# ultimate_Co-Op_v2_0.net
KiCad netlist of a schematic drawn in EAGLE
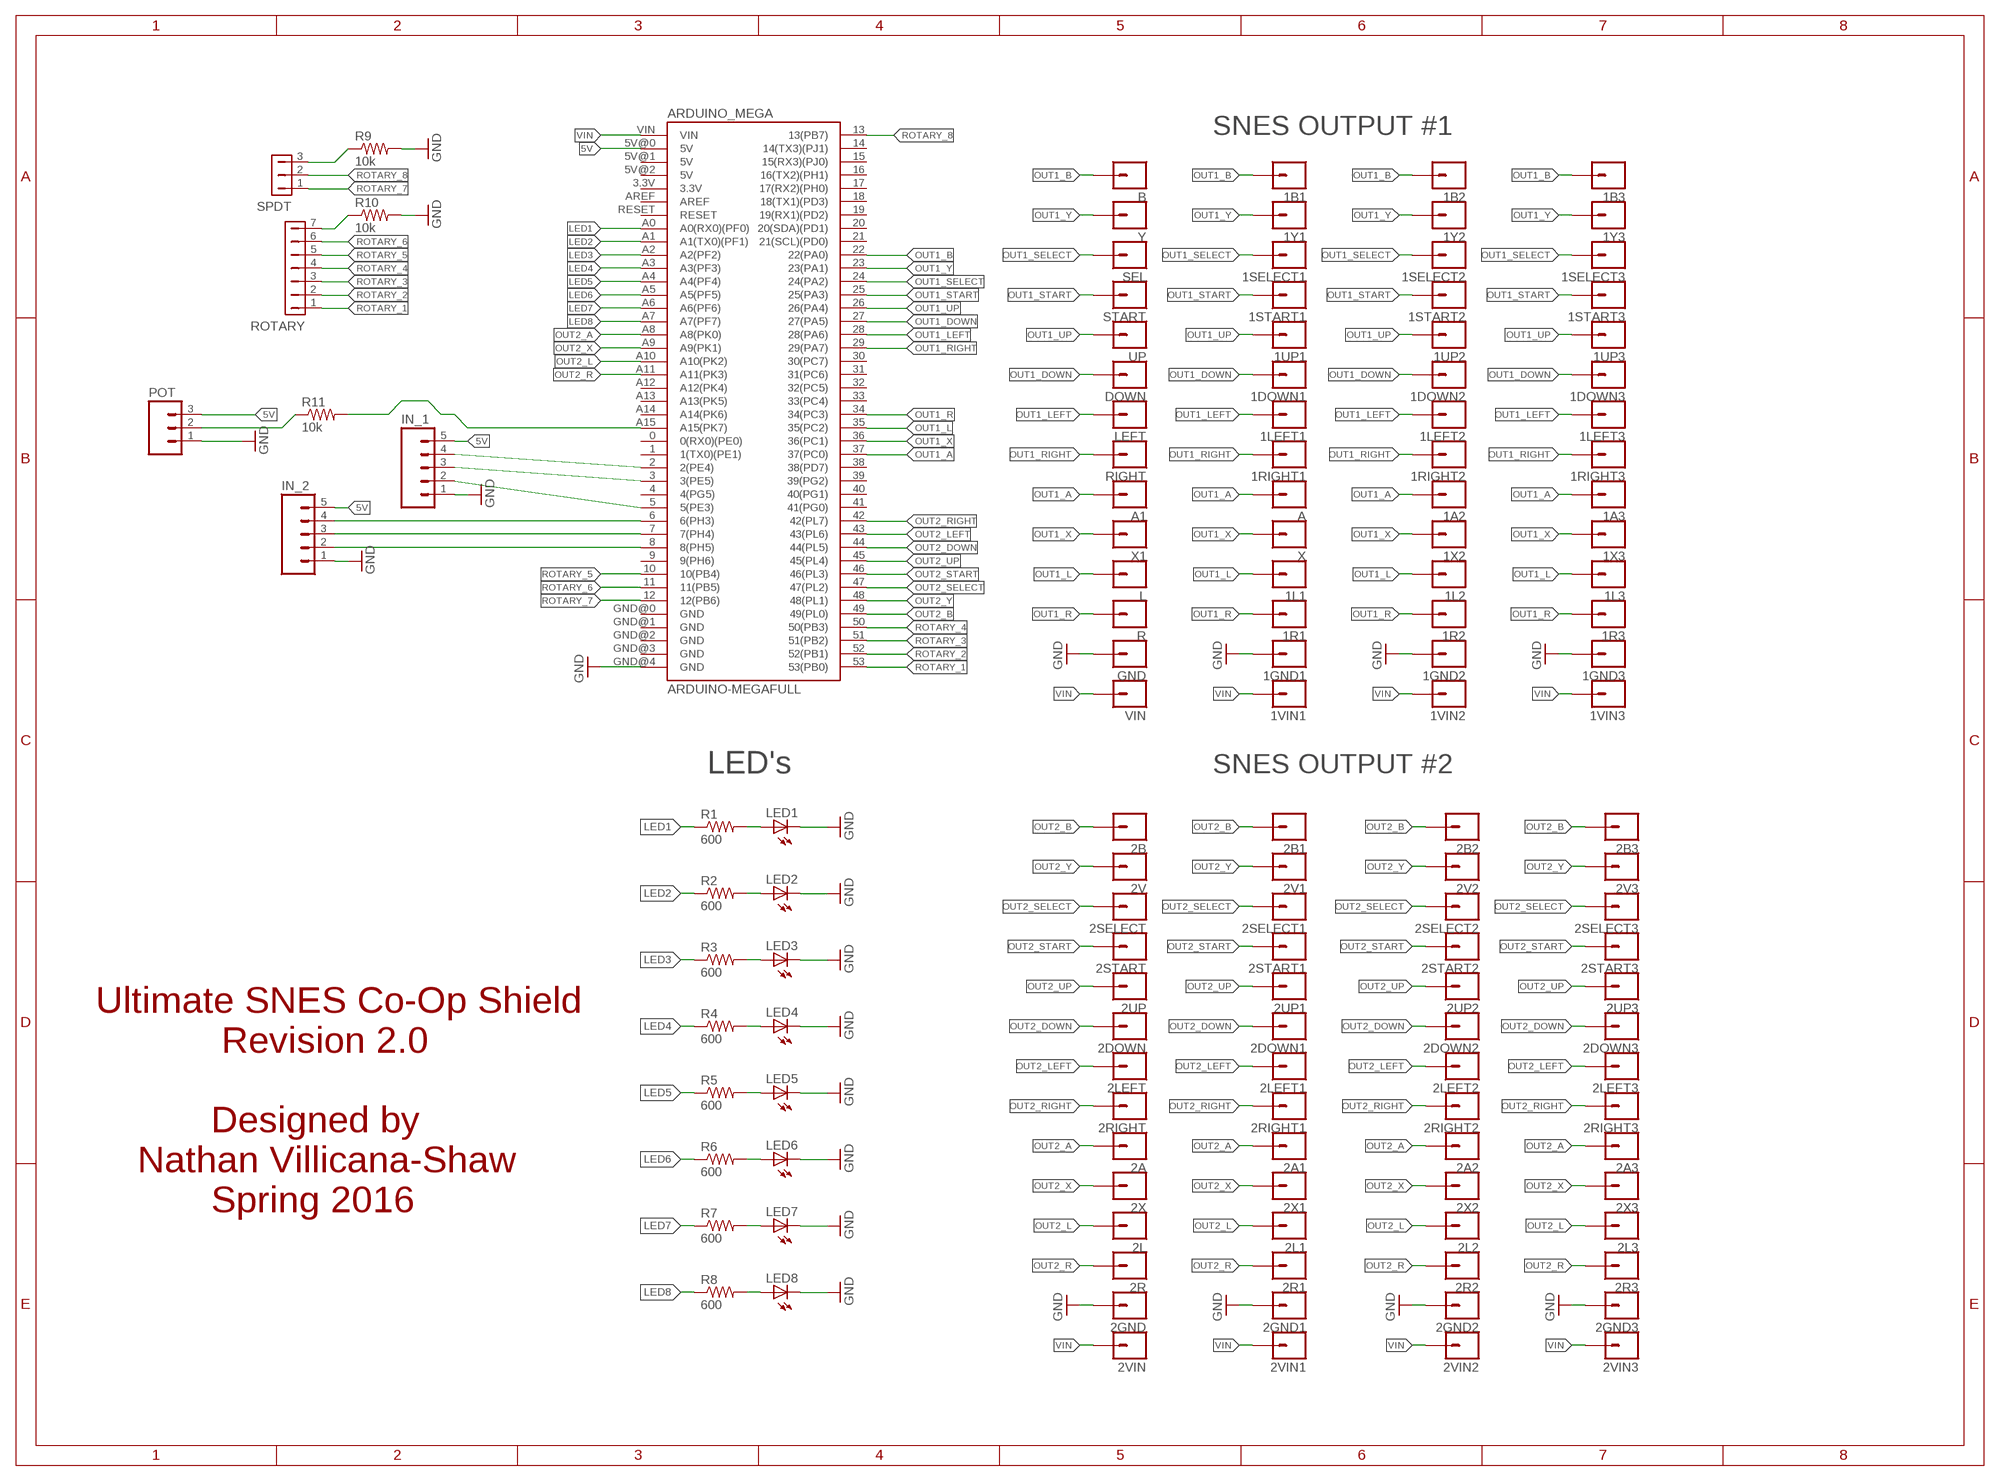
[diagram p0: schematic, sheet 1]

(export (version "E")
  (design (tool "Eeschema 10.0.6"))
  (components
    (comp (ref "1A2")
      (value "M01PTH")
      (footprint "eagle-import:1X01")
      (libsource (lib "eagle-import") (part "M01PTH"))
    )
    (comp (ref "1A3")
      (value "M01PTH")
      (footprint "eagle-import:1X01")
      (libsource (lib "eagle-import") (part "M01PTH"))
    )
    (comp (ref "1B1")
      (value "M01PTH")
      (footprint "eagle-import:1X01")
      (libsource (lib "eagle-import") (part "M01PTH"))
    )
    (comp (ref "1B2")
      (value "M01PTH")
      (footprint "eagle-import:1X01")
      (libsource (lib "eagle-import") (part "M01PTH"))
    )
    (comp (ref "1B3")
      (value "M01PTH")
      (footprint "eagle-import:1X01")
      (libsource (lib "eagle-import") (part "M01PTH"))
    )
    (comp (ref "1DOWN1")
      (value "M01PTH")
      (footprint "eagle-import:1X01")
      (libsource (lib "eagle-import") (part "M01PTH"))
    )
    (comp (ref "1DOWN2")
      (value "M01PTH")
      (footprint "eagle-import:1X01")
      (libsource (lib "eagle-import") (part "M01PTH"))
    )
    (comp (ref "1DOWN3")
      (value "M01PTH")
      (footprint "eagle-import:1X01")
      (libsource (lib "eagle-import") (part "M01PTH"))
    )
    (comp (ref "1GND1")
      (value "M01PTH")
      (footprint "eagle-import:1X01")
      (libsource (lib "eagle-import") (part "M01PTH"))
    )
    (comp (ref "1GND2")
      (value "M01PTH")
      (footprint "eagle-import:1X01")
      (libsource (lib "eagle-import") (part "M01PTH"))
    )
    (comp (ref "1GND3")
      (value "M01PTH")
      (footprint "eagle-import:1X01")
      (libsource (lib "eagle-import") (part "M01PTH"))
    )
    (comp (ref "1L1")
      (value "M01PTH")
      (footprint "eagle-import:1X01")
      (libsource (lib "eagle-import") (part "M01PTH"))
    )
    (comp (ref "1L2")
      (value "M01PTH")
      (footprint "eagle-import:1X01")
      (libsource (lib "eagle-import") (part "M01PTH"))
    )
    (comp (ref "1L3")
      (value "M01PTH")
      (footprint "eagle-import:1X01")
      (libsource (lib "eagle-import") (part "M01PTH"))
    )
    (comp (ref "1LEFT1")
      (value "M01PTH")
      (footprint "eagle-import:1X01")
      (libsource (lib "eagle-import") (part "M01PTH"))
    )
    (comp (ref "1LEFT2")
      (value "M01PTH")
      (footprint "eagle-import:1X01")
      (libsource (lib "eagle-import") (part "M01PTH"))
    )
    (comp (ref "1LEFT3")
      (value "M01PTH")
      (footprint "eagle-import:1X01")
      (libsource (lib "eagle-import") (part "M01PTH"))
    )
    (comp (ref "1R1")
      (value "M01PTH")
      (footprint "eagle-import:1X01")
      (libsource (lib "eagle-import") (part "M01PTH"))
    )
    (comp (ref "1R2")
      (value "M01PTH")
      (footprint "eagle-import:1X01")
      (libsource (lib "eagle-import") (part "M01PTH"))
    )
    (comp (ref "1R3")
      (value "M01PTH")
      (footprint "eagle-import:1X01")
      (libsource (lib "eagle-import") (part "M01PTH"))
    )
    (comp (ref "1RIGHT1")
      (value "M01PTH")
      (footprint "eagle-import:1X01")
      (libsource (lib "eagle-import") (part "M01PTH"))
    )
    (comp (ref "1RIGHT2")
      (value "M01PTH")
      (footprint "eagle-import:1X01")
      (libsource (lib "eagle-import") (part "M01PTH"))
    )
    (comp (ref "1RIGHT3")
      (value "M01PTH")
      (footprint "eagle-import:1X01")
      (libsource (lib "eagle-import") (part "M01PTH"))
    )
    (comp (ref "1SELECT1")
      (value "M01PTH")
      (footprint "eagle-import:1X01")
      (libsource (lib "eagle-import") (part "M01PTH"))
    )
    (comp (ref "1SELECT2")
      (value "M01PTH")
      (footprint "eagle-import:1X01")
      (libsource (lib "eagle-import") (part "M01PTH"))
    )
    (comp (ref "1SELECT3")
      (value "M01PTH")
      (footprint "eagle-import:1X01")
      (libsource (lib "eagle-import") (part "M01PTH"))
    )
    (comp (ref "1START1")
      (value "M01PTH")
      (footprint "eagle-import:1X01")
      (libsource (lib "eagle-import") (part "M01PTH"))
    )
    (comp (ref "1START2")
      (value "M01PTH")
      (footprint "eagle-import:1X01")
      (libsource (lib "eagle-import") (part "M01PTH"))
    )
    (comp (ref "1START3")
      (value "M01PTH")
      (footprint "eagle-import:1X01")
      (libsource (lib "eagle-import") (part "M01PTH"))
    )
    (comp (ref "1UP1")
      (value "M01PTH")
      (footprint "eagle-import:1X01")
      (libsource (lib "eagle-import") (part "M01PTH"))
    )
    (comp (ref "1UP2")
      (value "M01PTH")
      (footprint "eagle-import:1X01")
      (libsource (lib "eagle-import") (part "M01PTH"))
    )
    (comp (ref "1UP3")
      (value "M01PTH")
      (footprint "eagle-import:1X01")
      (libsource (lib "eagle-import") (part "M01PTH"))
    )
    (comp (ref "1VIN1")
      (value "M01PTH")
      (footprint "eagle-import:1X01")
      (libsource (lib "eagle-import") (part "M01PTH"))
    )
    (comp (ref "1VIN2")
      (value "M01PTH")
      (footprint "eagle-import:1X01")
      (libsource (lib "eagle-import") (part "M01PTH"))
    )
    (comp (ref "1VIN3")
      (value "M01PTH")
      (footprint "eagle-import:1X01")
      (libsource (lib "eagle-import") (part "M01PTH"))
    )
    (comp (ref "1X2")
      (value "M01PTH")
      (footprint "eagle-import:1X01")
      (libsource (lib "eagle-import") (part "M01PTH"))
    )
    (comp (ref "1X3")
      (value "M01PTH")
      (footprint "eagle-import:1X01")
      (libsource (lib "eagle-import") (part "M01PTH"))
    )
    (comp (ref "1Y1")
      (value "M01PTH")
      (footprint "eagle-import:1X01")
      (libsource (lib "eagle-import") (part "M01PTH"))
    )
    (comp (ref "1Y2")
      (value "M01PTH")
      (footprint "eagle-import:1X01")
      (libsource (lib "eagle-import") (part "M01PTH"))
    )
    (comp (ref "1Y3")
      (value "M01PTH")
      (footprint "eagle-import:1X01")
      (libsource (lib "eagle-import") (part "M01PTH"))
    )
    (comp (ref "2A")
      (value "M01PTH")
      (footprint "eagle-import:1X01")
      (libsource (lib "eagle-import") (part "M01PTH"))
    )
    (comp (ref "2A1")
      (value "M01PTH")
      (footprint "eagle-import:1X01")
      (libsource (lib "eagle-import") (part "M01PTH"))
    )
    (comp (ref "2A2")
      (value "M01PTH")
      (footprint "eagle-import:1X01")
      (libsource (lib "eagle-import") (part "M01PTH"))
    )
    (comp (ref "2A3")
      (value "M01PTH")
      (footprint "eagle-import:1X01")
      (libsource (lib "eagle-import") (part "M01PTH"))
    )
    (comp (ref "2B")
      (value "M01PTH")
      (footprint "eagle-import:1X01")
      (libsource (lib "eagle-import") (part "M01PTH"))
    )
    (comp (ref "2B1")
      (value "M01PTH")
      (footprint "eagle-import:1X01")
      (libsource (lib "eagle-import") (part "M01PTH"))
    )
    (comp (ref "2B2")
      (value "M01PTH")
      (footprint "eagle-import:1X01")
      (libsource (lib "eagle-import") (part "M01PTH"))
    )
    (comp (ref "2B3")
      (value "M01PTH")
      (footprint "eagle-import:1X01")
      (libsource (lib "eagle-import") (part "M01PTH"))
    )
    (comp (ref "2DOWN")
      (value "M01PTH")
      (footprint "eagle-import:1X01")
      (libsource (lib "eagle-import") (part "M01PTH"))
    )
    (comp (ref "2DOWN1")
      (value "M01PTH")
      (footprint "eagle-import:1X01")
      (libsource (lib "eagle-import") (part "M01PTH"))
    )
    (comp (ref "2DOWN2")
      (value "M01PTH")
      (footprint "eagle-import:1X01")
      (libsource (lib "eagle-import") (part "M01PTH"))
    )
    (comp (ref "2DOWN3")
      (value "M01PTH")
      (footprint "eagle-import:1X01")
      (libsource (lib "eagle-import") (part "M01PTH"))
    )
    (comp (ref "2GND")
      (value "M01PTH")
      (footprint "eagle-import:1X01")
      (libsource (lib "eagle-import") (part "M01PTH"))
    )
    (comp (ref "2GND1")
      (value "M01PTH")
      (footprint "eagle-import:1X01")
      (libsource (lib "eagle-import") (part "M01PTH"))
    )
    (comp (ref "2GND2")
      (value "M01PTH")
      (footprint "eagle-import:1X01")
      (libsource (lib "eagle-import") (part "M01PTH"))
    )
    (comp (ref "2GND3")
      (value "M01PTH")
      (footprint "eagle-import:1X01")
      (libsource (lib "eagle-import") (part "M01PTH"))
    )
    (comp (ref "2L")
      (value "M01PTH")
      (footprint "eagle-import:1X01")
      (libsource (lib "eagle-import") (part "M01PTH"))
    )
    (comp (ref "2L1")
      (value "M01PTH")
      (footprint "eagle-import:1X01")
      (libsource (lib "eagle-import") (part "M01PTH"))
    )
    (comp (ref "2L2")
      (value "M01PTH")
      (footprint "eagle-import:1X01")
      (libsource (lib "eagle-import") (part "M01PTH"))
    )
    (comp (ref "2L3")
      (value "M01PTH")
      (footprint "eagle-import:1X01")
      (libsource (lib "eagle-import") (part "M01PTH"))
    )
    (comp (ref "2LEFT")
      (value "M01PTH")
      (footprint "eagle-import:1X01")
      (libsource (lib "eagle-import") (part "M01PTH"))
    )
    (comp (ref "2LEFT1")
      (value "M01PTH")
      (footprint "eagle-import:1X01")
      (libsource (lib "eagle-import") (part "M01PTH"))
    )
    (comp (ref "2LEFT2")
      (value "M01PTH")
      (footprint "eagle-import:1X01")
      (libsource (lib "eagle-import") (part "M01PTH"))
    )
    (comp (ref "2LEFT3")
      (value "M01PTH")
      (footprint "eagle-import:1X01")
      (libsource (lib "eagle-import") (part "M01PTH"))
    )
    (comp (ref "2R")
      (value "M01PTH")
      (footprint "eagle-import:1X01")
      (libsource (lib "eagle-import") (part "M01PTH"))
    )
    (comp (ref "2R1")
      (value "M01PTH")
      (footprint "eagle-import:1X01")
      (libsource (lib "eagle-import") (part "M01PTH"))
    )
    (comp (ref "2R2")
      (value "M01PTH")
      (footprint "eagle-import:1X01")
      (libsource (lib "eagle-import") (part "M01PTH"))
    )
    (comp (ref "2R3")
      (value "M01PTH")
      (footprint "eagle-import:1X01")
      (libsource (lib "eagle-import") (part "M01PTH"))
    )
    (comp (ref "2RIGHT")
      (value "M01PTH")
      (footprint "eagle-import:1X01")
      (libsource (lib "eagle-import") (part "M01PTH"))
    )
    (comp (ref "2RIGHT1")
      (value "M01PTH")
      (footprint "eagle-import:1X01")
      (libsource (lib "eagle-import") (part "M01PTH"))
    )
    (comp (ref "2RIGHT2")
      (value "M01PTH")
      (footprint "eagle-import:1X01")
      (libsource (lib "eagle-import") (part "M01PTH"))
    )
    (comp (ref "2RIGHT3")
      (value "M01PTH")
      (footprint "eagle-import:1X01")
      (libsource (lib "eagle-import") (part "M01PTH"))
    )
    (comp (ref "2SELECT")
      (value "M01PTH")
      (footprint "eagle-import:1X01")
      (libsource (lib "eagle-import") (part "M01PTH"))
    )
    (comp (ref "2SELECT1")
      (value "M01PTH")
      (footprint "eagle-import:1X01")
      (libsource (lib "eagle-import") (part "M01PTH"))
    )
    (comp (ref "2SELECT2")
      (value "M01PTH")
      (footprint "eagle-import:1X01")
      (libsource (lib "eagle-import") (part "M01PTH"))
    )
    (comp (ref "2SELECT3")
      (value "M01PTH")
      (footprint "eagle-import:1X01")
      (libsource (lib "eagle-import") (part "M01PTH"))
    )
    (comp (ref "2START")
      (value "M01PTH")
      (footprint "eagle-import:1X01")
      (libsource (lib "eagle-import") (part "M01PTH"))
    )
    (comp (ref "2START1")
      (value "M01PTH")
      (footprint "eagle-import:1X01")
      (libsource (lib "eagle-import") (part "M01PTH"))
    )
    (comp (ref "2START2")
      (value "M01PTH")
      (footprint "eagle-import:1X01")
      (libsource (lib "eagle-import") (part "M01PTH"))
    )
    (comp (ref "2START3")
      (value "M01PTH")
      (footprint "eagle-import:1X01")
      (libsource (lib "eagle-import") (part "M01PTH"))
    )
    (comp (ref "2UP")
      (value "M01PTH")
      (footprint "eagle-import:1X01")
      (libsource (lib "eagle-import") (part "M01PTH"))
    )
    (comp (ref "2UP1")
      (value "M01PTH")
      (footprint "eagle-import:1X01")
      (libsource (lib "eagle-import") (part "M01PTH"))
    )
    (comp (ref "2UP2")
      (value "M01PTH")
      (footprint "eagle-import:1X01")
      (libsource (lib "eagle-import") (part "M01PTH"))
    )
    (comp (ref "2UP3")
      (value "M01PTH")
      (footprint "eagle-import:1X01")
      (libsource (lib "eagle-import") (part "M01PTH"))
    )
    (comp (ref "2V")
      (value "M01PTH")
      (footprint "eagle-import:1X01")
      (libsource (lib "eagle-import") (part "M01PTH"))
    )
    (comp (ref "2V1")
      (value "M01PTH")
      (footprint "eagle-import:1X01")
      (libsource (lib "eagle-import") (part "M01PTH"))
    )
    (comp (ref "2V2")
      (value "M01PTH")
      (footprint "eagle-import:1X01")
      (libsource (lib "eagle-import") (part "M01PTH"))
    )
    (comp (ref "2V3")
      (value "M01PTH")
      (footprint "eagle-import:1X01")
      (libsource (lib "eagle-import") (part "M01PTH"))
    )
    (comp (ref "2VIN")
      (value "M01PTH")
      (footprint "eagle-import:1X01")
      (libsource (lib "eagle-import") (part "M01PTH"))
    )
    (comp (ref "2VIN1")
      (value "M01PTH")
      (footprint "eagle-import:1X01")
      (libsource (lib "eagle-import") (part "M01PTH"))
    )
    (comp (ref "2VIN2")
      (value "M01PTH")
      (footprint "eagle-import:1X01")
      (libsource (lib "eagle-import") (part "M01PTH"))
    )
    (comp (ref "2VIN3")
      (value "M01PTH")
      (footprint "eagle-import:1X01")
      (libsource (lib "eagle-import") (part "M01PTH"))
    )
    (comp (ref "2X")
      (value "M01PTH")
      (footprint "eagle-import:1X01")
      (libsource (lib "eagle-import") (part "M01PTH"))
    )
    (comp (ref "2X1")
      (value "M01PTH")
      (footprint "eagle-import:1X01")
      (libsource (lib "eagle-import") (part "M01PTH"))
    )
    (comp (ref "2X2")
      (value "M01PTH")
      (footprint "eagle-import:1X01")
      (libsource (lib "eagle-import") (part "M01PTH"))
    )
    (comp (ref "2X3")
      (value "M01PTH")
      (footprint "eagle-import:1X01")
      (libsource (lib "eagle-import") (part "M01PTH"))
    )
    (comp (ref "A")
      (value "M01PTH")
      (footprint "eagle-import:1X01")
      (libsource (lib "eagle-import") (part "M01PTH"))
    )
    (comp (ref "A1")
      (value "M01PTH")
      (footprint "eagle-import:1X01")
      (libsource (lib "eagle-import") (part "M01PTH"))
    )
    (comp (ref "ARDUINO_MEGA")
      (value "ARDUINO-MEGAFULL")
      (footprint "eagle-import:ARDUINO_MEGA")
      (libsource (lib "eagle-import") (part "ARDUINO-MEGAFULL"))
    )
    (comp (ref "B")
      (value "M01PTH")
      (footprint "eagle-import:1X01")
      (libsource (lib "eagle-import") (part "M01PTH"))
    )
    (comp (ref "DOWN")
      (value "M01PTH")
      (footprint "eagle-import:1X01")
      (libsource (lib "eagle-import") (part "M01PTH"))
    )
    (comp (ref "GND")
      (value "M01PTH")
      (footprint "eagle-import:1X01")
      (libsource (lib "eagle-import") (part "M01PTH"))
    )
    (comp (ref "IN_1")
      (value "M05PTH")
      (footprint "eagle-import:1X05")
      (libsource (lib "eagle-import") (part "M05PTH"))
    )
    (comp (ref "IN_2")
      (value "M05PTH")
      (footprint "eagle-import:1X05")
      (libsource (lib "eagle-import") (part "M05PTH"))
    )
    (comp (ref "L")
      (value "M01PTH")
      (footprint "eagle-import:1X01")
      (libsource (lib "eagle-import") (part "M01PTH"))
    )
    (comp (ref "LED1")
      (value "LED5MM")
      (footprint "eagle-import:LED5MM")
      (libsource (lib "eagle-import") (part "LED5MM"))
    )
    (comp (ref "LED2")
      (value "LED5MM")
      (footprint "eagle-import:LED5MM")
      (libsource (lib "eagle-import") (part "LED5MM"))
    )
    (comp (ref "LED3")
      (value "LED5MM")
      (footprint "eagle-import:LED5MM")
      (libsource (lib "eagle-import") (part "LED5MM"))
    )
    (comp (ref "LED4")
      (value "LED5MM")
      (footprint "eagle-import:LED5MM")
      (libsource (lib "eagle-import") (part "LED5MM"))
    )
    (comp (ref "LED5")
      (value "LED5MM")
      (footprint "eagle-import:LED5MM")
      (libsource (lib "eagle-import") (part "LED5MM"))
    )
    (comp (ref "LED6")
      (value "LED5MM")
      (footprint "eagle-import:LED5MM")
      (libsource (lib "eagle-import") (part "LED5MM"))
    )
    (comp (ref "LED7")
      (value "LED5MM")
      (footprint "eagle-import:LED5MM")
      (libsource (lib "eagle-import") (part "LED5MM"))
    )
    (comp (ref "LED8")
      (value "LED5MM")
      (footprint "eagle-import:LED5MM")
      (libsource (lib "eagle-import") (part "LED5MM"))
    )
    (comp (ref "LEFT")
      (value "M01PTH")
      (footprint "eagle-import:1X01")
      (libsource (lib "eagle-import") (part "M01PTH"))
    )
    (comp (ref "POT")
      (value "M03LONGPADS")
      (footprint "eagle-import:1X03_LONGPADS")
      (libsource (lib "eagle-import") (part "M03LONGPADS"))
    )
    (comp (ref "R")
      (value "M01PTH")
      (footprint "eagle-import:1X01")
      (libsource (lib "eagle-import") (part "M01PTH"))
    )
    (comp (ref "R1")
      (value "600")
      (footprint "eagle-import:0204_7")
      (libsource (lib "eagle-import") (part "R-US_0204/7"))
    )
    (comp (ref "R2")
      (value "600")
      (footprint "eagle-import:0204_7")
      (libsource (lib "eagle-import") (part "R-US_0204/7"))
    )
    (comp (ref "R3")
      (value "600")
      (footprint "eagle-import:0204_7")
      (libsource (lib "eagle-import") (part "R-US_0204/7"))
    )
    (comp (ref "R4")
      (value "600")
      (footprint "eagle-import:0204_7")
      (libsource (lib "eagle-import") (part "R-US_0204/7"))
    )
    (comp (ref "R5")
      (value "600")
      (footprint "eagle-import:0204_7")
      (libsource (lib "eagle-import") (part "R-US_0204/7"))
    )
    (comp (ref "R6")
      (value "600")
      (footprint "eagle-import:0204_7")
      (libsource (lib "eagle-import") (part "R-US_0204/7"))
    )
    (comp (ref "R7")
      (value "600")
      (footprint "eagle-import:0204_7")
      (libsource (lib "eagle-import") (part "R-US_0204/7"))
    )
    (comp (ref "R8")
      (value "600")
      (footprint "eagle-import:0204_7")
      (libsource (lib "eagle-import") (part "R-US_0204/7"))
    )
    (comp (ref "R9")
      (value "10k")
      (footprint "eagle-import:0204_7")
      (libsource (lib "eagle-import") (part "R-US_0204/7"))
    )
    (comp (ref "R10")
      (value "10k")
      (footprint "eagle-import:0204_7")
      (libsource (lib "eagle-import") (part "R-US_0204/7"))
    )
    (comp (ref "R11")
      (value "10k")
      (footprint "eagle-import:0204_7")
      (libsource (lib "eagle-import") (part "R-US_0204/7"))
    )
    (comp (ref "RIGHT")
      (value "M01PTH")
      (footprint "eagle-import:1X01")
      (libsource (lib "eagle-import") (part "M01PTH"))
    )
    (comp (ref "ROTARY")
      (value "HDR-1X7-MTE-100")
      (footprint "eagle-import:MTE-100-7V")
      (libsource (lib "eagle-import") (part "HDR-1X7-MTE-100"))
    )
    (comp (ref "SEL")
      (value "M01PTH")
      (footprint "eagle-import:1X01")
      (libsource (lib "eagle-import") (part "M01PTH"))
    )
    (comp (ref "SPDT")
      (value "HDR-1X3-MTA-100")
      (footprint "eagle-import:MTA-100-3V")
      (libsource (lib "eagle-import") (part "HDR-1X3-MTA-100"))
    )
    (comp (ref "START")
      (value "M01PTH")
      (footprint "eagle-import:1X01")
      (libsource (lib "eagle-import") (part "M01PTH"))
    )
    (comp (ref "UP")
      (value "M01PTH")
      (footprint "eagle-import:1X01")
      (libsource (lib "eagle-import") (part "M01PTH"))
    )
    (comp (ref "VIN")
      (value "M01PTH")
      (footprint "eagle-import:1X01")
      (libsource (lib "eagle-import") (part "M01PTH"))
    )
    (comp (ref "X")
      (value "M01PTH")
      (footprint "eagle-import:1X01")
      (libsource (lib "eagle-import") (part "M01PTH"))
    )
    (comp (ref "X1")
      (value "M01PTH")
      (footprint "eagle-import:1X01")
      (libsource (lib "eagle-import") (part "M01PTH"))
    )
    (comp (ref "Y")
      (value "M01PTH")
      (footprint "eagle-import:1X01")
      (libsource (lib "eagle-import") (part "M01PTH"))
    )
  )
  (nets
    (net (code "1") (name "5V") (class "Default")
      (node (ref "ARDUINO_MEGA") (pin "5V@0") (pinfunction "5V_5V@0") (pintype "bidirectional"))
      (node (ref "IN_1") (pin "5") (pinfunction "5_5") (pintype "passive"))
      (node (ref "IN_2") (pin "5") (pinfunction "5_5") (pintype "passive"))
      (node (ref "POT") (pin "3") (pinfunction "3_3") (pintype "passive"))
    )
    (net (code "2") (name "GND") (class "Default")
      (node (ref "1GND1") (pin "1") (pinfunction "1_1") (pintype "passive"))
      (node (ref "1GND2") (pin "1") (pinfunction "1_1") (pintype "passive"))
      (node (ref "1GND3") (pin "1") (pinfunction "1_1") (pintype "passive"))
      (node (ref "2GND") (pin "1") (pinfunction "1_1") (pintype "passive"))
      (node (ref "2GND1") (pin "1") (pinfunction "1_1") (pintype "passive"))
      (node (ref "2GND2") (pin "1") (pinfunction "1_1") (pintype "passive"))
      (node (ref "2GND3") (pin "1") (pinfunction "1_1") (pintype "passive"))
      (node (ref "ARDUINO_MEGA") (pin "GND@4") (pinfunction "GND_GND@4") (pintype "bidirectional"))
      (node (ref "GND") (pin "1") (pinfunction "1_1") (pintype "passive"))
      (node (ref "IN_1") (pin "1") (pinfunction "1_1") (pintype "passive"))
      (node (ref "IN_2") (pin "1") (pinfunction "1_1") (pintype "passive"))
      (node (ref "LED1") (pin "K") (pinfunction "C_K") (pintype "passive"))
      (node (ref "LED2") (pin "K") (pinfunction "C_K") (pintype "passive"))
      (node (ref "LED3") (pin "K") (pinfunction "C_K") (pintype "passive"))
      (node (ref "LED4") (pin "K") (pinfunction "C_K") (pintype "passive"))
      (node (ref "LED5") (pin "K") (pinfunction "C_K") (pintype "passive"))
      (node (ref "LED6") (pin "K") (pinfunction "C_K") (pintype "passive"))
      (node (ref "LED7") (pin "K") (pinfunction "C_K") (pintype "passive"))
      (node (ref "LED8") (pin "K") (pinfunction "C_K") (pintype "passive"))
      (node (ref "POT") (pin "1") (pinfunction "1_1") (pintype "passive"))
      (node (ref "R10") (pin "2") (pinfunction "2_2") (pintype "passive"))
      (node (ref "R9") (pin "2") (pinfunction "2_2") (pintype "passive"))
    )
    (net (code "3") (name "LED1") (class "Default")
      (node (ref "ARDUINO_MEGA") (pin "A0") (pinfunction "A0(RX0)(PF0)_A0") (pintype "bidirectional"))
      (node (ref "R1") (pin "1") (pinfunction "1_1") (pintype "passive"))
    )
    (net (code "4") (name "LED2") (class "Default")
      (node (ref "ARDUINO_MEGA") (pin "A1") (pinfunction "A1(TX0)(PF1)_A1") (pintype "bidirectional"))
      (node (ref "R2") (pin "1") (pinfunction "1_1") (pintype "passive"))
    )
    (net (code "5") (name "LED3") (class "Default")
      (node (ref "ARDUINO_MEGA") (pin "A2") (pinfunction "A2(PF2)_A2") (pintype "bidirectional"))
      (node (ref "R3") (pin "1") (pinfunction "1_1") (pintype "passive"))
    )
    (net (code "6") (name "LED4") (class "Default")
      (node (ref "ARDUINO_MEGA") (pin "A3") (pinfunction "A3(PF3)_A3") (pintype "bidirectional"))
      (node (ref "R4") (pin "1") (pinfunction "1_1") (pintype "passive"))
    )
    (net (code "7") (name "LED5") (class "Default")
      (node (ref "ARDUINO_MEGA") (pin "A4") (pinfunction "A4(PF4)_A4") (pintype "bidirectional"))
      (node (ref "R5") (pin "1") (pinfunction "1_1") (pintype "passive"))
    )
    (net (code "8") (name "LED6") (class "Default")
      (node (ref "ARDUINO_MEGA") (pin "A5") (pinfunction "A5(PF5)_A5") (pintype "bidirectional"))
      (node (ref "R6") (pin "1") (pinfunction "1_1") (pintype "passive"))
    )
    (net (code "9") (name "LED7") (class "Default")
      (node (ref "ARDUINO_MEGA") (pin "A6") (pinfunction "A6(PF6)_A6") (pintype "bidirectional"))
      (node (ref "R7") (pin "1") (pinfunction "1_1") (pintype "passive"))
    )
    (net (code "10") (name "LED8") (class "Default")
      (node (ref "ARDUINO_MEGA") (pin "A7") (pinfunction "A7(PF7)_A7") (pintype "bidirectional"))
      (node (ref "R8") (pin "1") (pinfunction "1_1") (pintype "passive"))
    )
    (net (code "11") (name "Net-(ARDUINO_MEGA-2(PE4))") (class "Default")
      (node (ref "ARDUINO_MEGA") (pin "2") (pinfunction "2(PE4)_2") (pintype "bidirectional"))
      (node (ref "IN_1") (pin "4") (pinfunction "4_4") (pintype "passive"))
    )
    (net (code "12") (name "Net-(ARDUINO_MEGA-3(PE5))") (class "Default")
      (node (ref "ARDUINO_MEGA") (pin "3") (pinfunction "3(PE5)_3") (pintype "bidirectional"))
      (node (ref "IN_1") (pin "3") (pinfunction "3_3") (pintype "passive"))
    )
    (net (code "13") (name "Net-(ARDUINO_MEGA-5(PE3))") (class "Default")
      (node (ref "ARDUINO_MEGA") (pin "5") (pinfunction "5(PE3)_5") (pintype "bidirectional"))
      (node (ref "IN_1") (pin "2") (pinfunction "2_2") (pintype "passive"))
    )
    (net (code "14") (name "Net-(ARDUINO_MEGA-6(PH3))") (class "Default")
      (node (ref "ARDUINO_MEGA") (pin "6") (pinfunction "6(PH3)_6") (pintype "bidirectional"))
      (node (ref "IN_2") (pin "4") (pinfunction "4_4") (pintype "passive"))
    )
    (net (code "15") (name "Net-(ARDUINO_MEGA-7(PH4))") (class "Default")
      (node (ref "ARDUINO_MEGA") (pin "7") (pinfunction "7(PH4)_7") (pintype "bidirectional"))
      (node (ref "IN_2") (pin "3") (pinfunction "3_3") (pintype "passive"))
    )
    (net (code "16") (name "Net-(ARDUINO_MEGA-8(PH5))") (class "Default")
      (node (ref "ARDUINO_MEGA") (pin "8") (pinfunction "8(PH5)_8") (pintype "bidirectional"))
      (node (ref "IN_2") (pin "2") (pinfunction "2_2") (pintype "passive"))
    )
    (net (code "17") (name "Net-(ARDUINO_MEGA-A15(PK7))") (class "Default")
      (node (ref "ARDUINO_MEGA") (pin "A15") (pinfunction "A15(PK7)_A15") (pintype "bidirectional"))
      (node (ref "R11") (pin "2") (pinfunction "2_2") (pintype "passive"))
    )
    (net (code "18") (name "Net-(LED1-PadA)") (class "Default")
      (node (ref "LED1") (pin "A") (pinfunction "A_A") (pintype "passive"))
      (node (ref "R1") (pin "2") (pinfunction "2_2") (pintype "passive"))
    )
    (net (code "19") (name "Net-(LED2-PadA)") (class "Default")
      (node (ref "LED2") (pin "A") (pinfunction "A_A") (pintype "passive"))
      (node (ref "R2") (pin "2") (pinfunction "2_2") (pintype "passive"))
    )
    (net (code "20") (name "Net-(LED3-PadA)") (class "Default")
      (node (ref "LED3") (pin "A") (pinfunction "A_A") (pintype "passive"))
      (node (ref "R3") (pin "2") (pinfunction "2_2") (pintype "passive"))
    )
    (net (code "21") (name "Net-(LED4-PadA)") (class "Default")
      (node (ref "LED4") (pin "A") (pinfunction "A_A") (pintype "passive"))
      (node (ref "R4") (pin "2") (pinfunction "2_2") (pintype "passive"))
    )
    (net (code "22") (name "Net-(LED5-PadA)") (class "Default")
      (node (ref "LED5") (pin "A") (pinfunction "A_A") (pintype "passive"))
      (node (ref "R5") (pin "2") (pinfunction "2_2") (pintype "passive"))
    )
    (net (code "23") (name "Net-(LED6-PadA)") (class "Default")
      (node (ref "LED6") (pin "A") (pinfunction "A_A") (pintype "passive"))
      (node (ref "R6") (pin "2") (pinfunction "2_2") (pintype "passive"))
    )
    (net (code "24") (name "Net-(LED7-PadA)") (class "Default")
      (node (ref "LED7") (pin "A") (pinfunction "A_A") (pintype "passive"))
      (node (ref "R7") (pin "2") (pinfunction "2_2") (pintype "passive"))
    )
    (net (code "25") (name "Net-(LED8-PadA)") (class "Default")
      (node (ref "LED8") (pin "A") (pinfunction "A_A") (pintype "passive"))
      (node (ref "R8") (pin "2") (pinfunction "2_2") (pintype "passive"))
    )
    (net (code "26") (name "Net-(POT-Pad2)") (class "Default")
      (node (ref "POT") (pin "2") (pinfunction "2_2") (pintype "passive"))
      (node (ref "R11") (pin "1") (pinfunction "1_1") (pintype "passive"))
    )
    (net (code "27") (name "Net-(R9-Pad1)") (class "Default")
      (node (ref "R9") (pin "1") (pinfunction "1_1") (pintype "passive"))
      (node (ref "SPDT") (pin "3") (pinfunction "3_3") (pintype "passive"))
    )
    (net (code "28") (name "Net-(R10-Pad1)") (class "Default")
      (node (ref "R10") (pin "1") (pinfunction "1_1") (pintype "passive"))
      (node (ref "ROTARY") (pin "7") (pinfunction "7_7") (pintype "passive"))
    )
    (net (code "29") (name "OUT1_A") (class "Default")
      (node (ref "1A2") (pin "1") (pinfunction "1_1") (pintype "passive"))
      (node (ref "1A3") (pin "1") (pinfunction "1_1") (pintype "passive"))
      (node (ref "A") (pin "1") (pinfunction "1_1") (pintype "passive"))
      (node (ref "A1") (pin "1") (pinfunction "1_1") (pintype "passive"))
      (node (ref "ARDUINO_MEGA") (pin "37") (pinfunction "37(PC0)_37") (pintype "bidirectional"))
    )
    (net (code "30") (name "OUT1_B") (class "Default")
      (node (ref "1B1") (pin "1") (pinfunction "1_1") (pintype "passive"))
      (node (ref "1B2") (pin "1") (pinfunction "1_1") (pintype "passive"))
      (node (ref "1B3") (pin "1") (pinfunction "1_1") (pintype "passive"))
      (node (ref "ARDUINO_MEGA") (pin "22") (pinfunction "22(PA0)_22") (pintype "bidirectional"))
      (node (ref "B") (pin "1") (pinfunction "1_1") (pintype "passive"))
    )
    (net (code "31") (name "OUT1_DOWN") (class "Default")
      (node (ref "1DOWN1") (pin "1") (pinfunction "1_1") (pintype "passive"))
      (node (ref "1DOWN2") (pin "1") (pinfunction "1_1") (pintype "passive"))
      (node (ref "1DOWN3") (pin "1") (pinfunction "1_1") (pintype "passive"))
      (node (ref "ARDUINO_MEGA") (pin "27") (pinfunction "27(PA5)_27") (pintype "bidirectional"))
      (node (ref "DOWN") (pin "1") (pinfunction "1_1") (pintype "passive"))
    )
    (net (code "32") (name "OUT1_L") (class "Default")
      (node (ref "1L1") (pin "1") (pinfunction "1_1") (pintype "passive"))
      (node (ref "1L2") (pin "1") (pinfunction "1_1") (pintype "passive"))
      (node (ref "1L3") (pin "1") (pinfunction "1_1") (pintype "passive"))
      (node (ref "ARDUINO_MEGA") (pin "35") (pinfunction "35(PC2)_35") (pintype "bidirectional"))
      (node (ref "L") (pin "1") (pinfunction "1_1") (pintype "passive"))
    )
    (net (code "33") (name "OUT1_LEFT") (class "Default")
      (node (ref "1LEFT1") (pin "1") (pinfunction "1_1") (pintype "passive"))
      (node (ref "1LEFT2") (pin "1") (pinfunction "1_1") (pintype "passive"))
      (node (ref "1LEFT3") (pin "1") (pinfunction "1_1") (pintype "passive"))
      (node (ref "ARDUINO_MEGA") (pin "28") (pinfunction "28(PA6)_28") (pintype "bidirectional"))
      (node (ref "LEFT") (pin "1") (pinfunction "1_1") (pintype "passive"))
    )
    (net (code "34") (name "OUT1_R") (class "Default")
      (node (ref "1R1") (pin "1") (pinfunction "1_1") (pintype "passive"))
      (node (ref "1R2") (pin "1") (pinfunction "1_1") (pintype "passive"))
      (node (ref "1R3") (pin "1") (pinfunction "1_1") (pintype "passive"))
      (node (ref "ARDUINO_MEGA") (pin "34") (pinfunction "34(PC3)_34") (pintype "bidirectional"))
      (node (ref "R") (pin "1") (pinfunction "1_1") (pintype "passive"))
    )
    (net (code "35") (name "OUT1_RIGHT") (class "Default")
      (node (ref "1RIGHT1") (pin "1") (pinfunction "1_1") (pintype "passive"))
      (node (ref "1RIGHT2") (pin "1") (pinfunction "1_1") (pintype "passive"))
      (node (ref "1RIGHT3") (pin "1") (pinfunction "1_1") (pintype "passive"))
      (node (ref "ARDUINO_MEGA") (pin "29") (pinfunction "29(PA7)_29") (pintype "bidirectional"))
      (node (ref "RIGHT") (pin "1") (pinfunction "1_1") (pintype "passive"))
    )
    (net (code "36") (name "OUT1_SELECT") (class "Default")
      (node (ref "1SELECT1") (pin "1") (pinfunction "1_1") (pintype "passive"))
      (node (ref "1SELECT2") (pin "1") (pinfunction "1_1") (pintype "passive"))
      (node (ref "1SELECT3") (pin "1") (pinfunction "1_1") (pintype "passive"))
      (node (ref "ARDUINO_MEGA") (pin "24") (pinfunction "24(PA2)_24") (pintype "bidirectional"))
      (node (ref "SEL") (pin "1") (pinfunction "1_1") (pintype "passive"))
    )
    (net (code "37") (name "OUT1_START") (class "Default")
      (node (ref "1START1") (pin "1") (pinfunction "1_1") (pintype "passive"))
      (node (ref "1START2") (pin "1") (pinfunction "1_1") (pintype "passive"))
      (node (ref "1START3") (pin "1") (pinfunction "1_1") (pintype "passive"))
      (node (ref "ARDUINO_MEGA") (pin "25") (pinfunction "25(PA3)_25") (pintype "bidirectional"))
      (node (ref "START") (pin "1") (pinfunction "1_1") (pintype "passive"))
    )
    (net (code "38") (name "OUT1_UP") (class "Default")
      (node (ref "1UP1") (pin "1") (pinfunction "1_1") (pintype "passive"))
      (node (ref "1UP2") (pin "1") (pinfunction "1_1") (pintype "passive"))
      (node (ref "1UP3") (pin "1") (pinfunction "1_1") (pintype "passive"))
      (node (ref "ARDUINO_MEGA") (pin "26") (pinfunction "26(PA4)_26") (pintype "bidirectional"))
      (node (ref "UP") (pin "1") (pinfunction "1_1") (pintype "passive"))
    )
    (net (code "39") (name "OUT1_X") (class "Default")
      (node (ref "1X2") (pin "1") (pinfunction "1_1") (pintype "passive"))
      (node (ref "1X3") (pin "1") (pinfunction "1_1") (pintype "passive"))
      (node (ref "ARDUINO_MEGA") (pin "36") (pinfunction "36(PC1)_36") (pintype "bidirectional"))
      (node (ref "X") (pin "1") (pinfunction "1_1") (pintype "passive"))
      (node (ref "X1") (pin "1") (pinfunction "1_1") (pintype "passive"))
    )
    (net (code "40") (name "OUT1_Y") (class "Default")
      (node (ref "1Y1") (pin "1") (pinfunction "1_1") (pintype "passive"))
      (node (ref "1Y2") (pin "1") (pinfunction "1_1") (pintype "passive"))
      (node (ref "1Y3") (pin "1") (pinfunction "1_1") (pintype "passive"))
      (node (ref "ARDUINO_MEGA") (pin "23") (pinfunction "23(PA1)_23") (pintype "bidirectional"))
      (node (ref "Y") (pin "1") (pinfunction "1_1") (pintype "passive"))
    )
    (net (code "41") (name "OUT2_A") (class "Default")
      (node (ref "2A") (pin "1") (pinfunction "1_1") (pintype "passive"))
      (node (ref "2A1") (pin "1") (pinfunction "1_1") (pintype "passive"))
      (node (ref "2A2") (pin "1") (pinfunction "1_1") (pintype "passive"))
      (node (ref "2A3") (pin "1") (pinfunction "1_1") (pintype "passive"))
      (node (ref "ARDUINO_MEGA") (pin "A8") (pinfunction "A8(PK0)_A8") (pintype "bidirectional"))
    )
    (net (code "42") (name "OUT2_B") (class "Default")
      (node (ref "2B") (pin "1") (pinfunction "1_1") (pintype "passive"))
      (node (ref "2B1") (pin "1") (pinfunction "1_1") (pintype "passive"))
      (node (ref "2B2") (pin "1") (pinfunction "1_1") (pintype "passive"))
      (node (ref "2B3") (pin "1") (pinfunction "1_1") (pintype "passive"))
      (node (ref "ARDUINO_MEGA") (pin "49") (pinfunction "49(PL0)_49") (pintype "bidirectional"))
    )
    (net (code "43") (name "OUT2_DOWN") (class "Default")
      (node (ref "2DOWN") (pin "1") (pinfunction "1_1") (pintype "passive"))
      (node (ref "2DOWN1") (pin "1") (pinfunction "1_1") (pintype "passive"))
      (node (ref "2DOWN2") (pin "1") (pinfunction "1_1") (pintype "passive"))
      (node (ref "2DOWN3") (pin "1") (pinfunction "1_1") (pintype "passive"))
      (node (ref "ARDUINO_MEGA") (pin "44") (pinfunction "44(PL5)_44") (pintype "bidirectional"))
    )
    (net (code "44") (name "OUT2_L") (class "Default")
      (node (ref "2L") (pin "1") (pinfunction "1_1") (pintype "passive"))
      (node (ref "2L1") (pin "1") (pinfunction "1_1") (pintype "passive"))
      (node (ref "2L2") (pin "1") (pinfunction "1_1") (pintype "passive"))
      (node (ref "2L3") (pin "1") (pinfunction "1_1") (pintype "passive"))
      (node (ref "ARDUINO_MEGA") (pin "A10") (pinfunction "A10(PK2)_A10") (pintype "bidirectional"))
    )
    (net (code "45") (name "OUT2_LEFT") (class "Default")
      (node (ref "2LEFT") (pin "1") (pinfunction "1_1") (pintype "passive"))
      (node (ref "2LEFT1") (pin "1") (pinfunction "1_1") (pintype "passive"))
      (node (ref "2LEFT2") (pin "1") (pinfunction "1_1") (pintype "passive"))
      (node (ref "2LEFT3") (pin "1") (pinfunction "1_1") (pintype "passive"))
      (node (ref "ARDUINO_MEGA") (pin "43") (pinfunction "43(PL6)_43") (pintype "bidirectional"))
    )
    (net (code "46") (name "OUT2_R") (class "Default")
      (node (ref "2R") (pin "1") (pinfunction "1_1") (pintype "passive"))
      (node (ref "2R1") (pin "1") (pinfunction "1_1") (pintype "passive"))
      (node (ref "2R2") (pin "1") (pinfunction "1_1") (pintype "passive"))
      (node (ref "2R3") (pin "1") (pinfunction "1_1") (pintype "passive"))
      (node (ref "ARDUINO_MEGA") (pin "A11") (pinfunction "A11(PK3)_A11") (pintype "bidirectional"))
    )
    (net (code "47") (name "OUT2_RIGHT") (class "Default")
      (node (ref "2RIGHT") (pin "1") (pinfunction "1_1") (pintype "passive"))
      (node (ref "2RIGHT1") (pin "1") (pinfunction "1_1") (pintype "passive"))
      (node (ref "2RIGHT2") (pin "1") (pinfunction "1_1") (pintype "passive"))
      (node (ref "2RIGHT3") (pin "1") (pinfunction "1_1") (pintype "passive"))
      (node (ref "ARDUINO_MEGA") (pin "42") (pinfunction "42(PL7)_42") (pintype "bidirectional"))
    )
    (net (code "48") (name "OUT2_SELECT") (class "Default")
      (node (ref "2SELECT") (pin "1") (pinfunction "1_1") (pintype "passive"))
      (node (ref "2SELECT1") (pin "1") (pinfunction "1_1") (pintype "passive"))
      (node (ref "2SELECT2") (pin "1") (pinfunction "1_1") (pintype "passive"))
      (node (ref "2SELECT3") (pin "1") (pinfunction "1_1") (pintype "passive"))
      (node (ref "ARDUINO_MEGA") (pin "47") (pinfunction "47(PL2)_47") (pintype "bidirectional"))
    )
    (net (code "49") (name "OUT2_START") (class "Default")
      (node (ref "2START") (pin "1") (pinfunction "1_1") (pintype "passive"))
      (node (ref "2START1") (pin "1") (pinfunction "1_1") (pintype "passive"))
      (node (ref "2START2") (pin "1") (pinfunction "1_1") (pintype "passive"))
      (node (ref "2START3") (pin "1") (pinfunction "1_1") (pintype "passive"))
      (node (ref "ARDUINO_MEGA") (pin "46") (pinfunction "46(PL3)_46") (pintype "bidirectional"))
    )
    (net (code "50") (name "OUT2_UP") (class "Default")
      (node (ref "2UP") (pin "1") (pinfunction "1_1") (pintype "passive"))
      (node (ref "2UP1") (pin "1") (pinfunction "1_1") (pintype "passive"))
      (node (ref "2UP2") (pin "1") (pinfunction "1_1") (pintype "passive"))
      (node (ref "2UP3") (pin "1") (pinfunction "1_1") (pintype "passive"))
      (node (ref "ARDUINO_MEGA") (pin "45") (pinfunction "45(PL4)_45") (pintype "bidirectional"))
    )
    (net (code "51") (name "OUT2_X") (class "Default")
      (node (ref "2X") (pin "1") (pinfunction "1_1") (pintype "passive"))
      (node (ref "2X1") (pin "1") (pinfunction "1_1") (pintype "passive"))
      (node (ref "2X2") (pin "1") (pinfunction "1_1") (pintype "passive"))
      (node (ref "2X3") (pin "1") (pinfunction "1_1") (pintype "passive"))
      (node (ref "ARDUINO_MEGA") (pin "A9") (pinfunction "A9(PK1)_A9") (pintype "bidirectional"))
    )
    (net (code "52") (name "OUT2_Y") (class "Default")
      (node (ref "2V") (pin "1") (pinfunction "1_1") (pintype "passive"))
      (node (ref "2V1") (pin "1") (pinfunction "1_1") (pintype "passive"))
      (node (ref "2V2") (pin "1") (pinfunction "1_1") (pintype "passive"))
      (node (ref "2V3") (pin "1") (pinfunction "1_1") (pintype "passive"))
      (node (ref "ARDUINO_MEGA") (pin "48") (pinfunction "48(PL1)_48") (pintype "bidirectional"))
    )
    (net (code "53") (name "ROTARY_1") (class "Default")
      (node (ref "ARDUINO_MEGA") (pin "53") (pinfunction "53(PB0)_53") (pintype "bidirectional"))
      (node (ref "ROTARY") (pin "1") (pinfunction "1_1") (pintype "passive"))
    )
    (net (code "54") (name "ROTARY_2") (class "Default")
      (node (ref "ARDUINO_MEGA") (pin "52") (pinfunction "52(PB1)_52") (pintype "bidirectional"))
      (node (ref "ROTARY") (pin "2") (pinfunction "2_2") (pintype "passive"))
    )
    (net (code "55") (name "ROTARY_3") (class "Default")
      (node (ref "ARDUINO_MEGA") (pin "51") (pinfunction "51(PB2)_51") (pintype "bidirectional"))
      (node (ref "ROTARY") (pin "3") (pinfunction "3_3") (pintype "passive"))
    )
    (net (code "56") (name "ROTARY_4") (class "Default")
      (node (ref "ARDUINO_MEGA") (pin "50") (pinfunction "50(PB3)_50") (pintype "bidirectional"))
      (node (ref "ROTARY") (pin "4") (pinfunction "4_4") (pintype "passive"))
    )
    (net (code "57") (name "ROTARY_5") (class "Default")
      (node (ref "ARDUINO_MEGA") (pin "10") (pinfunction "10(PB4)_10") (pintype "bidirectional"))
      (node (ref "ROTARY") (pin "5") (pinfunction "5_5") (pintype "passive"))
    )
    (net (code "58") (name "ROTARY_6") (class "Default")
      (node (ref "ARDUINO_MEGA") (pin "11") (pinfunction "11(PB5)_11") (pintype "bidirectional"))
      (node (ref "ROTARY") (pin "6") (pinfunction "6_6") (pintype "passive"))
    )
    (net (code "59") (name "ROTARY_7") (class "Default")
      (node (ref "ARDUINO_MEGA") (pin "12") (pinfunction "12(PB6)_12") (pintype "bidirectional"))
      (node (ref "SPDT") (pin "1") (pinfunction "1_1") (pintype "passive"))
    )
    (net (code "60") (name "ROTARY_8") (class "Default")
      (node (ref "ARDUINO_MEGA") (pin "13") (pinfunction "13(PB7)_13") (pintype "bidirectional"))
      (node (ref "SPDT") (pin "2") (pinfunction "2_2") (pintype "passive"))
    )
    (net (code "61") (name "VIN") (class "Default")
      (node (ref "1VIN1") (pin "1") (pinfunction "1_1") (pintype "passive"))
      (node (ref "1VIN2") (pin "1") (pinfunction "1_1") (pintype "passive"))
      (node (ref "1VIN3") (pin "1") (pinfunction "1_1") (pintype "passive"))
      (node (ref "2VIN") (pin "1") (pinfunction "1_1") (pintype "passive"))
      (node (ref "2VIN1") (pin "1") (pinfunction "1_1") (pintype "passive"))
      (node (ref "2VIN2") (pin "1") (pinfunction "1_1") (pintype "passive"))
      (node (ref "2VIN3") (pin "1") (pinfunction "1_1") (pintype "passive"))
      (node (ref "ARDUINO_MEGA") (pin "VIN") (pinfunction "VIN_VIN") (pintype "bidirectional"))
      (node (ref "VIN") (pin "1") (pinfunction "1_1") (pintype "passive"))
    )
    (net (code "62") (name "unconnected-(ARDUINO_MEGA-0(RX0)(PE0)-Pad0)") (class "Default")
      (node (ref "ARDUINO_MEGA") (pin "0") (pinfunction "0(RX0)(PE0)_0") (pintype "bidirectional"))
    )
    (net (code "63") (name "unconnected-(ARDUINO_MEGA-1(TX0)(PE1)-Pad1)") (class "Default")
      (node (ref "ARDUINO_MEGA") (pin "1") (pinfunction "1(TX0)(PE1)_1") (pintype "bidirectional"))
    )
    (net (code "64") (name "unconnected-(ARDUINO_MEGA-4(PG5)-Pad4)") (class "Default")
      (node (ref "ARDUINO_MEGA") (pin "4") (pinfunction "4(PG5)_4") (pintype "bidirectional"))
    )
    (net (code "65") (name "unconnected-(ARDUINO_MEGA-5V-Pad5V@1)") (class "Default")
      (node (ref "ARDUINO_MEGA") (pin "5V@1") (pinfunction "5V_5V@1") (pintype "bidirectional"))
    )
    (net (code "66") (name "unconnected-(ARDUINO_MEGA-5V-Pad5V@2)") (class "Default")
      (node (ref "ARDUINO_MEGA") (pin "5V@2") (pinfunction "5V_5V@2") (pintype "bidirectional"))
    )
    (net (code "67") (name "unconnected-(ARDUINO_MEGA-9(PH6)-Pad9)") (class "Default")
      (node (ref "ARDUINO_MEGA") (pin "9") (pinfunction "9(PH6)_9") (pintype "bidirectional"))
    )
    (net (code "68") (name "unconnected-(ARDUINO_MEGA-14(TX3)(PJ1)-Pad14)") (class "Default")
      (node (ref "ARDUINO_MEGA") (pin "14") (pinfunction "14(TX3)(PJ1)_14") (pintype "bidirectional"))
    )
    (net (code "69") (name "unconnected-(ARDUINO_MEGA-15(RX3)(PJ0)-Pad15)") (class "Default")
      (node (ref "ARDUINO_MEGA") (pin "15") (pinfunction "15(RX3)(PJ0)_15") (pintype "bidirectional"))
    )
    (net (code "70") (name "unconnected-(ARDUINO_MEGA-16(TX2)(PH1)-Pad16)") (class "Default")
      (node (ref "ARDUINO_MEGA") (pin "16") (pinfunction "16(TX2)(PH1)_16") (pintype "bidirectional"))
    )
    (net (code "71") (name "unconnected-(ARDUINO_MEGA-17(RX2)(PH0)-Pad17)") (class "Default")
      (node (ref "ARDUINO_MEGA") (pin "17") (pinfunction "17(RX2)(PH0)_17") (pintype "bidirectional"))
    )
    (net (code "72") (name "unconnected-(ARDUINO_MEGA-18(TX1)(PD3)-Pad18)") (class "Default")
      (node (ref "ARDUINO_MEGA") (pin "18") (pinfunction "18(TX1)(PD3)_18") (pintype "bidirectional"))
    )
    (net (code "73") (name "unconnected-(ARDUINO_MEGA-19(RX1)(PD2)-Pad19)") (class "Default")
      (node (ref "ARDUINO_MEGA") (pin "19") (pinfunction "19(RX1)(PD2)_19") (pintype "bidirectional"))
    )
    (net (code "74") (name "unconnected-(ARDUINO_MEGA-20(SDA)(PD1)-Pad20)") (class "Default")
      (node (ref "ARDUINO_MEGA") (pin "20") (pinfunction "20(SDA)(PD1)_20") (pintype "bidirectional"))
    )
    (net (code "75") (name "unconnected-(ARDUINO_MEGA-21(SCL)(PD0)-Pad21)") (class "Default")
      (node (ref "ARDUINO_MEGA") (pin "21") (pinfunction "21(SCL)(PD0)_21") (pintype "bidirectional"))
    )
    (net (code "76") (name "unconnected-(ARDUINO_MEGA-30(PC7)-Pad30)") (class "Default")
      (node (ref "ARDUINO_MEGA") (pin "30") (pinfunction "30(PC7)_30") (pintype "bidirectional"))
    )
    (net (code "77") (name "unconnected-(ARDUINO_MEGA-31(PC6)-Pad31)") (class "Default")
      (node (ref "ARDUINO_MEGA") (pin "31") (pinfunction "31(PC6)_31") (pintype "bidirectional"))
    )
    (net (code "78") (name "unconnected-(ARDUINO_MEGA-32(PC5)-Pad32)") (class "Default")
      (node (ref "ARDUINO_MEGA") (pin "32") (pinfunction "32(PC5)_32") (pintype "bidirectional"))
    )
    (net (code "79") (name "unconnected-(ARDUINO_MEGA-33(PC4)-Pad33)") (class "Default")
      (node (ref "ARDUINO_MEGA") (pin "33") (pinfunction "33(PC4)_33") (pintype "bidirectional"))
    )
    (net (code "80") (name "unconnected-(ARDUINO_MEGA-38(PD7)-Pad38)") (class "Default")
      (node (ref "ARDUINO_MEGA") (pin "38") (pinfunction "38(PD7)_38") (pintype "bidirectional"))
    )
    (net (code "81") (name "unconnected-(ARDUINO_MEGA-39(PG2)-Pad39)") (class "Default")
      (node (ref "ARDUINO_MEGA") (pin "39") (pinfunction "39(PG2)_39") (pintype "bidirectional"))
    )
    (net (code "82") (name "unconnected-(ARDUINO_MEGA-40(PG1)-Pad40)") (class "Default")
      (node (ref "ARDUINO_MEGA") (pin "40") (pinfunction "40(PG1)_40") (pintype "bidirectional"))
    )
    (net (code "83") (name "unconnected-(ARDUINO_MEGA-41(PG0)-Pad41)") (class "Default")
      (node (ref "ARDUINO_MEGA") (pin "41") (pinfunction "41(PG0)_41") (pintype "bidirectional"))
    )
    (net (code "84") (name "unconnected-(ARDUINO_MEGA-A12(PK4)-PadA12)") (class "Default")
      (node (ref "ARDUINO_MEGA") (pin "A12") (pinfunction "A12(PK4)_A12") (pintype "bidirectional"))
    )
    (net (code "85") (name "unconnected-(ARDUINO_MEGA-A13(PK5)-PadA13)") (class "Default")
      (node (ref "ARDUINO_MEGA") (pin "A13") (pinfunction "A13(PK5)_A13") (pintype "bidirectional"))
    )
    (net (code "86") (name "unconnected-(ARDUINO_MEGA-A14(PK6)-PadA14)") (class "Default")
      (node (ref "ARDUINO_MEGA") (pin "A14") (pinfunction "A14(PK6)_A14") (pintype "bidirectional"))
    )
    (net (code "87") (name "unconnected-(ARDUINO_MEGA-GND-PadGND@0)") (class "Default")
      (node (ref "ARDUINO_MEGA") (pin "GND@0") (pinfunction "GND_GND@0") (pintype "bidirectional"))
    )
    (net (code "88") (name "unconnected-(ARDUINO_MEGA-GND-PadGND@1)") (class "Default")
      (node (ref "ARDUINO_MEGA") (pin "GND@1") (pinfunction "GND_GND@1") (pintype "bidirectional"))
    )
    (net (code "89") (name "unconnected-(ARDUINO_MEGA-GND-PadGND@2)") (class "Default")
      (node (ref "ARDUINO_MEGA") (pin "GND@2") (pinfunction "GND_GND@2") (pintype "bidirectional"))
    )
    (net (code "90") (name "unconnected-(ARDUINO_MEGA-GND-PadGND@3)") (class "Default")
      (node (ref "ARDUINO_MEGA") (pin "GND@3") (pinfunction "GND_GND@3") (pintype "bidirectional"))
    )
    (net (code "91") (name "unconnected-(ARDUINO_MEGA-Pad3.3V)") (class "Default")
      (node (ref "ARDUINO_MEGA") (pin "3.3V") (pinfunction "3.3V_3.3V") (pintype "bidirectional"))
    )
    (net (code "92") (name "unconnected-(ARDUINO_MEGA-PadAREF)") (class "Default")
      (node (ref "ARDUINO_MEGA") (pin "AREF") (pinfunction "AREF_AREF") (pintype "bidirectional"))
    )
    (net (code "93") (name "unconnected-(ARDUINO_MEGA-PadRESET)") (class "Default")
      (node (ref "ARDUINO_MEGA") (pin "RESET") (pinfunction "RESET_RESET") (pintype "bidirectional"))
    )
  )
)
